# BreadBoard.net
KiCad netlist of a schematic drawn in EAGLE
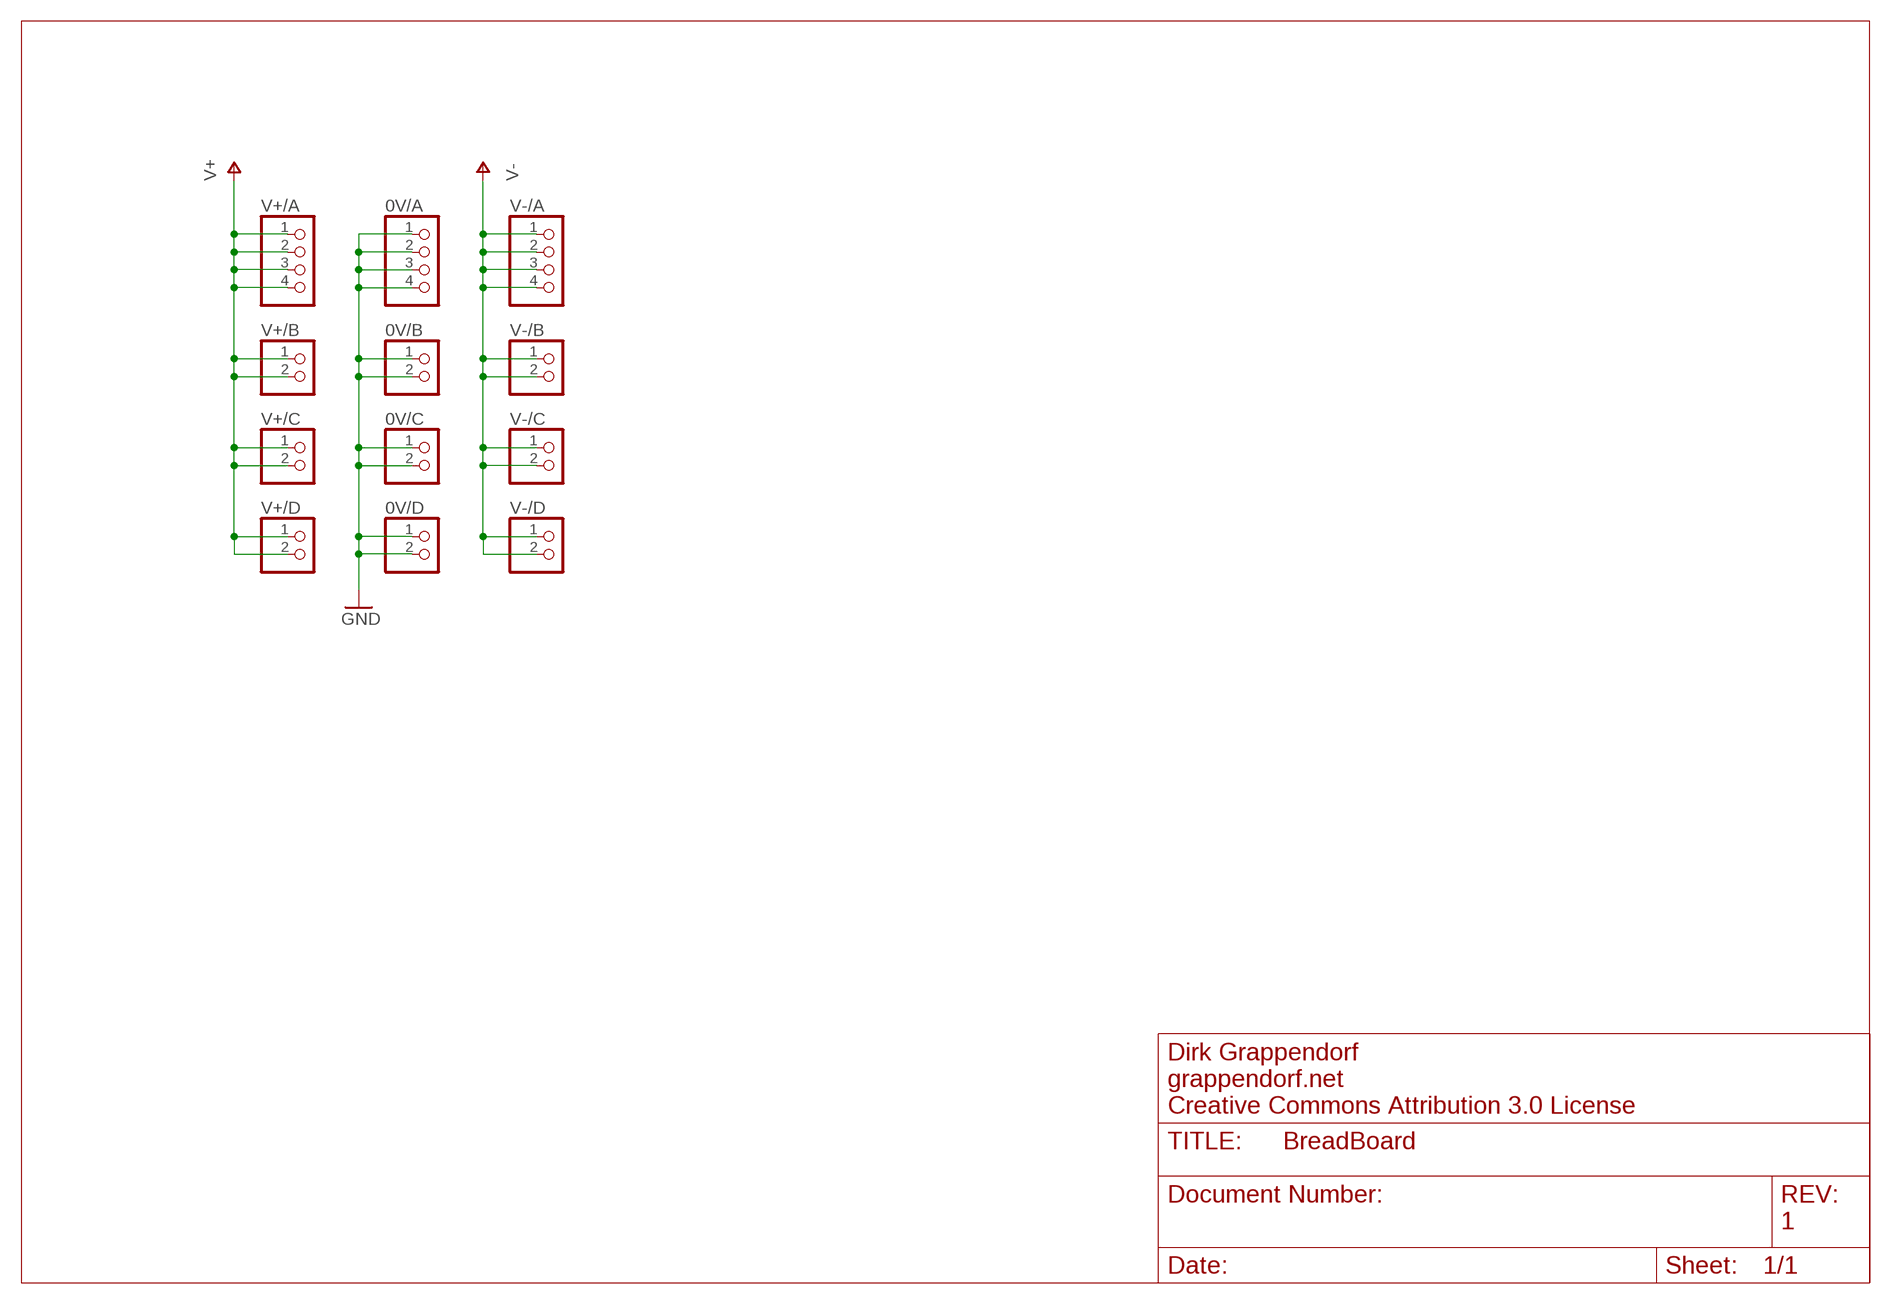
[diagram p0: schematic, sheet 1]

(export (version "E")
  (design (tool "Eeschema 10.0.6"))
  (components
    (comp (ref "0V/A")
      (value "PINHD-1X4")
      (footprint "eagle-import:1X04")
      (libsource (lib "eagle-import") (part "PINHD-1X4"))
    )
    (comp (ref "0V/B")
      (value "PINHD-1X2")
      (footprint "eagle-import:1X02")
      (libsource (lib "eagle-import") (part "PINHD-1X2"))
    )
    (comp (ref "0V/C")
      (value "PINHD-1X2")
      (footprint "eagle-import:1X02")
      (libsource (lib "eagle-import") (part "PINHD-1X2"))
    )
    (comp (ref "0V/D")
      (value "PINHD-1X2")
      (footprint "eagle-import:1X02")
      (libsource (lib "eagle-import") (part "PINHD-1X2"))
    )
    (comp (ref "V+/A")
      (value "PINHD-1X4")
      (footprint "eagle-import:1X04")
      (libsource (lib "eagle-import") (part "PINHD-1X4"))
    )
    (comp (ref "V+/B")
      (value "PINHD-1X2")
      (footprint "eagle-import:1X02")
      (libsource (lib "eagle-import") (part "PINHD-1X2"))
    )
    (comp (ref "V+/C")
      (value "PINHD-1X2")
      (footprint "eagle-import:1X02")
      (libsource (lib "eagle-import") (part "PINHD-1X2"))
    )
    (comp (ref "V+/D")
      (value "PINHD-1X2")
      (footprint "eagle-import:1X02")
      (libsource (lib "eagle-import") (part "PINHD-1X2"))
    )
    (comp (ref "V-/A")
      (value "PINHD-1X4")
      (footprint "eagle-import:1X04")
      (libsource (lib "eagle-import") (part "PINHD-1X4"))
    )
    (comp (ref "V-/B")
      (value "PINHD-1X2")
      (footprint "eagle-import:1X02")
      (libsource (lib "eagle-import") (part "PINHD-1X2"))
    )
    (comp (ref "V-/C")
      (value "PINHD-1X2")
      (footprint "eagle-import:1X02")
      (libsource (lib "eagle-import") (part "PINHD-1X2"))
    )
    (comp (ref "V-/D")
      (value "PINHD-1X2")
      (footprint "eagle-import:1X02")
      (libsource (lib "eagle-import") (part "PINHD-1X2"))
    )
  )
  (nets
    (net (code "1") (name "GND") (class "Default")
      (node (ref "0V/A") (pin "1") (pinfunction "1_1") (pintype "passive"))
      (node (ref "0V/A") (pin "2") (pinfunction "2_2") (pintype "passive"))
      (node (ref "0V/A") (pin "3") (pinfunction "3_3") (pintype "passive"))
      (node (ref "0V/A") (pin "4") (pinfunction "4_4") (pintype "passive"))
      (node (ref "0V/B") (pin "1") (pinfunction "1_1") (pintype "passive"))
      (node (ref "0V/B") (pin "2") (pinfunction "2_2") (pintype "passive"))
      (node (ref "0V/C") (pin "1") (pinfunction "1_1") (pintype "passive"))
      (node (ref "0V/C") (pin "2") (pinfunction "2_2") (pintype "passive"))
      (node (ref "0V/D") (pin "1") (pinfunction "1_1") (pintype "passive"))
      (node (ref "0V/D") (pin "2") (pinfunction "2_2") (pintype "passive"))
    )
    (net (code "2") (name "V+") (class "Default")
      (node (ref "V+/A") (pin "1") (pinfunction "1_1") (pintype "passive"))
      (node (ref "V+/A") (pin "2") (pinfunction "2_2") (pintype "passive"))
      (node (ref "V+/A") (pin "3") (pinfunction "3_3") (pintype "passive"))
      (node (ref "V+/A") (pin "4") (pinfunction "4_4") (pintype "passive"))
      (node (ref "V+/B") (pin "1") (pinfunction "1_1") (pintype "passive"))
      (node (ref "V+/B") (pin "2") (pinfunction "2_2") (pintype "passive"))
      (node (ref "V+/C") (pin "1") (pinfunction "1_1") (pintype "passive"))
      (node (ref "V+/C") (pin "2") (pinfunction "2_2") (pintype "passive"))
      (node (ref "V+/D") (pin "1") (pinfunction "1_1") (pintype "passive"))
      (node (ref "V+/D") (pin "2") (pinfunction "2_2") (pintype "passive"))
    )
    (net (code "3") (name "V-") (class "Default")
      (node (ref "V-/A") (pin "1") (pinfunction "1_1") (pintype "passive"))
      (node (ref "V-/A") (pin "2") (pinfunction "2_2") (pintype "passive"))
      (node (ref "V-/A") (pin "3") (pinfunction "3_3") (pintype "passive"))
      (node (ref "V-/A") (pin "4") (pinfunction "4_4") (pintype "passive"))
      (node (ref "V-/B") (pin "1") (pinfunction "1_1") (pintype "passive"))
      (node (ref "V-/B") (pin "2") (pinfunction "2_2") (pintype "passive"))
      (node (ref "V-/C") (pin "1") (pinfunction "1_1") (pintype "passive"))
      (node (ref "V-/C") (pin "2") (pinfunction "2_2") (pintype "passive"))
      (node (ref "V-/D") (pin "1") (pinfunction "1_1") (pintype "passive"))
      (node (ref "V-/D") (pin "2") (pinfunction "2_2") (pintype "passive"))
    )
  )
)
